# AnyTelemetry.net
KiCad netlist of a schematic drawn in EAGLE
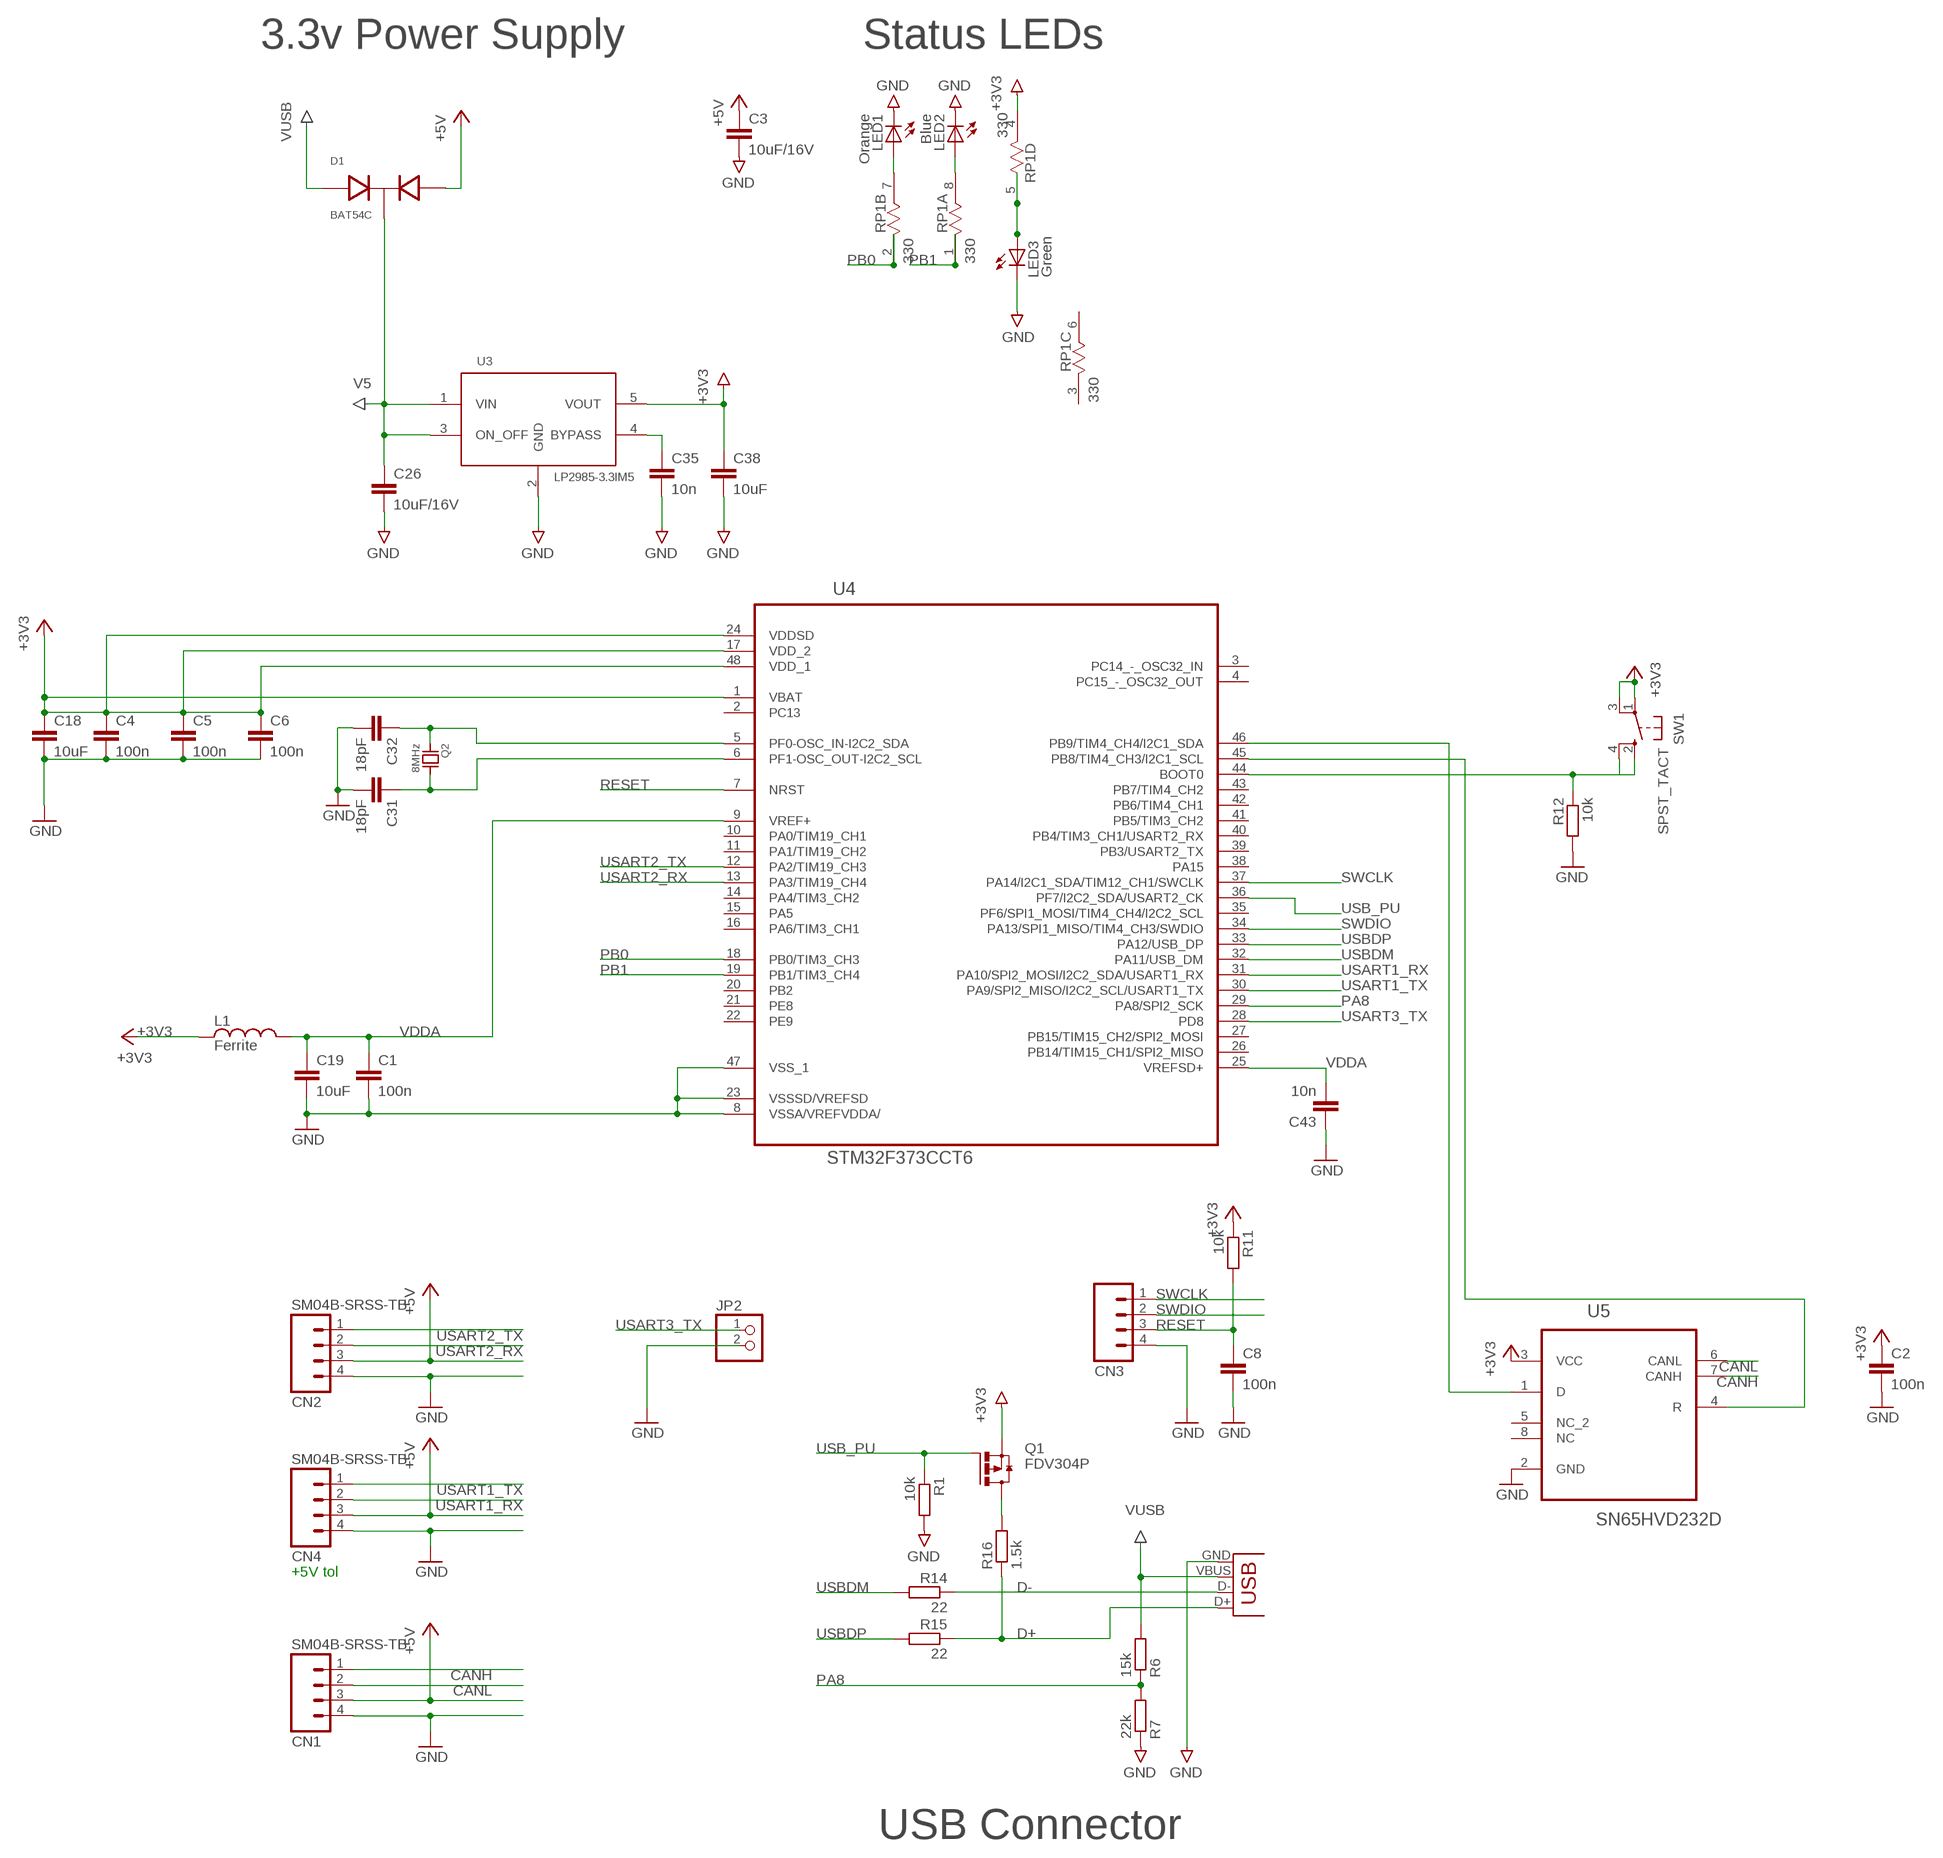
[diagram p0: schematic, sheet 1]

(export (version "E")
  (design (tool "Eeschema 10.0.6"))
  (components
    (comp (ref "C1")
      (value "100n")
      (footprint "eagle-import:0603")
      (libsource (lib "eagle-import") (part "CAPACITOR0603"))
    )
    (comp (ref "C2")
      (value "100n")
      (footprint "eagle-import:0603")
      (libsource (lib "eagle-import") (part "CAPACITOR0603"))
    )
    (comp (ref "C3")
      (value "10uF/16V")
      (footprint "eagle-import:C0805")
      (libsource (lib "eagle-import") (part "C-EUC0805"))
    )
    (comp (ref "C4")
      (value "100n")
      (footprint "eagle-import:0603")
      (libsource (lib "eagle-import") (part "CAPACITOR0603"))
    )
    (comp (ref "C5")
      (value "100n")
      (footprint "eagle-import:0603")
      (libsource (lib "eagle-import") (part "CAPACITOR0603"))
    )
    (comp (ref "C6")
      (value "100n")
      (footprint "eagle-import:0603")
      (libsource (lib "eagle-import") (part "CAPACITOR0603"))
    )
    (comp (ref "C8")
      (value "100n")
      (footprint "eagle-import:0603")
      (libsource (lib "eagle-import") (part "CAPACITOR0603"))
    )
    (comp (ref "C18")
      (value "10uF")
      (footprint "eagle-import:C0805")
      (libsource (lib "eagle-import") (part "C-EUC0805"))
    )
    (comp (ref "C19")
      (value "10uF")
      (footprint "eagle-import:C0805")
      (libsource (lib "eagle-import") (part "C-EUC0805"))
    )
    (comp (ref "C26")
      (value "10uF/16V")
      (footprint "eagle-import:C0805")
      (libsource (lib "eagle-import") (part "C-EUC0805"))
    )
    (comp (ref "C31")
      (value "18pF")
      (footprint "eagle-import:0603")
      (libsource (lib "eagle-import") (part "CAPACITOR0603"))
    )
    (comp (ref "C32")
      (value "18pF")
      (footprint "eagle-import:0603")
      (libsource (lib "eagle-import") (part "CAPACITOR0603"))
    )
    (comp (ref "C35")
      (value "10n")
      (footprint "eagle-import:C0603")
      (libsource (lib "eagle-import") (part "C-EUC0603"))
    )
    (comp (ref "C38")
      (value "10uF")
      (footprint "eagle-import:C0805")
      (libsource (lib "eagle-import") (part "C-EUC0805"))
    )
    (comp (ref "C43")
      (value "10n")
      (footprint "eagle-import:0603-CAP")
      (libsource (lib "eagle-import") (part "CAP0603-CAP"))
    )
    (comp (ref "CN1")
      (value "SM04B-SRSS-TB")
      (footprint "eagle-import:SM04B-SRSS-TB")
      (libsource (lib "eagle-import") (part "SM04B-SRSS-TB"))
    )
    (comp (ref "CN2")
      (value "SM04B-SRSS-TB")
      (footprint "eagle-import:SM04B-SRSS-TB")
      (libsource (lib "eagle-import") (part "SM04B-SRSS-TB"))
    )
    (comp (ref "CN3")
      (value "SM04B-SRSS-TB")
      (footprint "eagle-import:SM04B-SRSS-TB")
      (libsource (lib "eagle-import") (part "SM04B-SRSS-TB"))
    )
    (comp (ref "CN4")
      (value "SM04B-SRSS-TB")
      (footprint "eagle-import:SM04B-SRSS-TB")
      (libsource (lib "eagle-import") (part "SM04B-SRSS-TB"))
    )
    (comp (ref "D1")
      (value "BAT54C")
      (footprint "eagle-import:SOT23")
      (libsource (lib "eagle-import") (part "BAT54C"))
    )
    (comp (ref "JP2")
      (value "PINHD-1X02_2.54-S")
      (footprint "eagle-import:1X02-S")
      (libsource (lib "eagle-import") (part "PINHD-1X02_2.54-S"))
    )
    (comp (ref "L1")
      (value "Ferrite")
      (footprint "eagle-import:0603")
      (libsource (lib "eagle-import") (part "INDUCTOR0603"))
    )
    (comp (ref "LED1")
      (value "Orange")
      (footprint "eagle-import:CHIPLED_0603")
      (libsource (lib "eagle-import") (part "LEDCHIPLED_0603"))
    )
    (comp (ref "LED2")
      (value "Blue")
      (footprint "eagle-import:CHIPLED_0603")
      (libsource (lib "eagle-import") (part "LEDCHIPLED_0603"))
    )
    (comp (ref "LED3")
      (value "Green")
      (footprint "eagle-import:CHIPLED_0603")
      (libsource (lib "eagle-import") (part "LEDCHIPLED_0603"))
    )
    (comp (ref "Q1")
      (value "FDV304P")
      (footprint "eagle-import:SUPER-SOT3")
      (libsource (lib "eagle-import") (part "FDN360P"))
    )
    (comp (ref "Q2")
      (value "8MHz")
      (footprint "eagle-import:CRYSTAL-5X3")
      (libsource (lib "eagle-import") (part "CRYSTAL-5X3"))
    )
    (comp (ref "R1")
      (value "10k")
      (footprint "eagle-import:R0603")
      (libsource (lib "eagle-import") (part "R-EU_R0603"))
    )
    (comp (ref "R6")
      (value "15k")
      (footprint "eagle-import:R0603")
      (libsource (lib "eagle-import") (part "R-EU_R0603"))
    )
    (comp (ref "R7")
      (value "22k")
      (footprint "eagle-import:R0603")
      (libsource (lib "eagle-import") (part "R-EU_R0603"))
    )
    (comp (ref "R11")
      (value "10k")
      (footprint "eagle-import:R0603")
      (libsource (lib "eagle-import") (part "R-EU_R0603"))
    )
    (comp (ref "R12")
      (value "10k")
      (footprint "eagle-import:R0603")
      (libsource (lib "eagle-import") (part "R-EU_R0603"))
    )
    (comp (ref "R14")
      (value "22")
      (footprint "eagle-import:R0603")
      (libsource (lib "eagle-import") (part "R-EU_R0603"))
    )
    (comp (ref "R15")
      (value "22")
      (footprint "eagle-import:R0603")
      (libsource (lib "eagle-import") (part "R-EU_R0603"))
    )
    (comp (ref "R16")
      (value "1.5k")
      (footprint "eagle-import:R0603")
      (libsource (lib "eagle-import") (part "R-EU_R0603"))
    )
    (comp (ref "RP1")
      (value "330")
      (footprint "eagle-import:RES4NT")
      (libsource (lib "eagle-import") (part "RES4NT"))
    )
    (comp (ref "SW1")
      (value "SPST_TACT")
      (footprint "eagle-import:EVQ-PU")
      (libsource (lib "eagle-import") (part "SPST_TACT"))
    )
    (comp (ref "U3")
      (value "LP2985-3.3IM5")
      (footprint "eagle-import:SOT23-5")
      (libsource (lib "eagle-import") (part "LP2985-IM53.3"))
    )
    (comp (ref "U4")
      (value "STM32F373CCT6")
      (footprint "eagle-import:QFP50P900X900X160-48N")
      (libsource (lib "eagle-import") (part "STM32F373CCT6"))
    )
    (comp (ref "U5")
      (value "SN65HVD232D")
      (footprint "eagle-import:SOIC127P600X175-8N")
      (libsource (lib "eagle-import") (part "SN65HVD232D"))
    )
    (comp (ref "X2")
      (value "USBSMD")
      (footprint "eagle-import:USB-MINIB")
      (libsource (lib "eagle-import") (part "USBSMD"))
    )
  )
  (nets
    (net (code "1") (name "+3V3") (class "Default")
      (node (ref "C18") (pin "1") (pinfunction "1_1") (pintype "passive"))
      (node (ref "C2") (pin "1") (pinfunction "1_1") (pintype "passive"))
      (node (ref "C38") (pin "1") (pinfunction "1_1") (pintype "passive"))
      (node (ref "C4") (pin "1") (pinfunction "1_1") (pintype "passive"))
      (node (ref "C5") (pin "1") (pinfunction "1_1") (pintype "passive"))
      (node (ref "C6") (pin "1") (pinfunction "1_1") (pintype "passive"))
      (node (ref "L1") (pin "1") (pinfunction "1_1") (pintype "passive"))
      (node (ref "Q1") (pin "2") (pinfunction "S_2") (pintype "passive"))
      (node (ref "R11") (pin "1") (pinfunction "1_1") (pintype "passive"))
      (node (ref "RP1") (pin "4") (pinfunction "1_4") (pintype "passive"))
      (node (ref "SW1") (pin "1") (pinfunction "P_1") (pintype "passive"))
      (node (ref "SW1") (pin "3") (pinfunction "P1_3") (pintype "passive"))
      (node (ref "U3") (pin "5") (pinfunction "VOUT_5") (pintype "passive"))
      (node (ref "U4") (pin "1") (pinfunction "VBAT_1") (pintype "passive"))
      (node (ref "U4") (pin "17") (pinfunction "VDD_2_17") (pintype "power_in"))
      (node (ref "U4") (pin "24") (pinfunction "VDDSD_24") (pintype "power_in"))
      (node (ref "U4") (pin "48") (pinfunction "VDD_1_48") (pintype "power_in"))
      (node (ref "U5") (pin "3") (pinfunction "VCC_3") (pintype "power_in"))
    )
    (net (code "2") (name "+5V") (class "Default")
      (node (ref "C3") (pin "1") (pinfunction "1_1") (pintype "passive"))
      (node (ref "CN1") (pin "3") (pinfunction "3_3") (pintype "passive"))
      (node (ref "CN2") (pin "3") (pinfunction "3_3") (pintype "passive"))
      (node (ref "CN4") (pin "3") (pinfunction "3_3") (pintype "passive"))
      (node (ref "D1") (pin "2") (pinfunction "P$2_2") (pintype "input"))
    )
    (net (code "3") (name "/CANH") (class "Default")
      (node (ref "CN1") (pin "1") (pinfunction "1_1") (pintype "passive"))
      (node (ref "U5") (pin "7") (pinfunction "CANH_7") (pintype "output"))
    )
    (net (code "4") (name "/CANL") (class "Default")
      (node (ref "CN1") (pin "2") (pinfunction "2_2") (pintype "passive"))
      (node (ref "U5") (pin "6") (pinfunction "CANL_6") (pintype "output"))
    )
    (net (code "5") (name "/D+") (class "Default")
      (node (ref "R15") (pin "1") (pinfunction "1_1") (pintype "passive"))
      (node (ref "R16") (pin "1") (pinfunction "1_1") (pintype "passive"))
      (node (ref "X2") (pin "D+") (pinfunction "D+_D+") (pintype "bidirectional"))
    )
    (net (code "6") (name "/D-") (class "Default")
      (node (ref "R14") (pin "1") (pinfunction "1_1") (pintype "passive"))
      (node (ref "X2") (pin "D-") (pinfunction "D-_D-") (pintype "bidirectional"))
    )
    (net (code "7") (name "/PA8") (class "Default")
      (node (ref "R6") (pin "1") (pinfunction "1_1") (pintype "passive"))
      (node (ref "R7") (pin "2") (pinfunction "2_2") (pintype "passive"))
      (node (ref "U4") (pin "29") (pinfunction "PA8/SPI2_SCK_29") (pintype "bidirectional"))
    )
    (net (code "8") (name "/PB0") (class "Default")
      (node (ref "RP1") (pin "2") (pinfunction "1_2") (pintype "passive"))
      (node (ref "U4") (pin "18") (pinfunction "PB0/TIM3_CH3_18") (pintype "bidirectional"))
    )
    (net (code "9") (name "/PB1") (class "Default")
      (node (ref "RP1") (pin "1") (pinfunction "1_1") (pintype "passive"))
      (node (ref "U4") (pin "19") (pinfunction "PB1/TIM3_CH4_19") (pintype "bidirectional"))
    )
    (net (code "10") (name "/RESET") (class "Default")
      (node (ref "C8") (pin "1") (pinfunction "1_1") (pintype "passive"))
      (node (ref "CN3") (pin "3") (pinfunction "3_3") (pintype "passive"))
      (node (ref "R11") (pin "2") (pinfunction "2_2") (pintype "passive"))
      (node (ref "U4") (pin "7") (pinfunction "NRST_7") (pintype "passive"))
    )
    (net (code "11") (name "/SWCLK") (class "Default")
      (node (ref "CN3") (pin "1") (pinfunction "1_1") (pintype "passive"))
      (node (ref "U4") (pin "37") (pinfunction "PA14/I2C1_SDA/TIM12_CH1/SWCLK_37") (pintype "bidirectional"))
    )
    (net (code "12") (name "/SWDIO") (class "Default")
      (node (ref "CN3") (pin "2") (pinfunction "2_2") (pintype "passive"))
      (node (ref "U4") (pin "34") (pinfunction "PA13/SPI1_MISO/TIM4_CH3/SWDIO_34") (pintype "bidirectional"))
    )
    (net (code "13") (name "/USART1_RX") (class "Default")
      (node (ref "CN4") (pin "2") (pinfunction "2_2") (pintype "passive"))
      (node (ref "U4") (pin "31") (pinfunction "PA10/SPI2_MOSI/I2C2_SDA/USART1_RX_31") (pintype "bidirectional"))
    )
    (net (code "14") (name "/USART1_TX") (class "Default")
      (node (ref "CN4") (pin "1") (pinfunction "1_1") (pintype "passive"))
      (node (ref "U4") (pin "30") (pinfunction "PA9/SPI2_MISO/I2C2_SCL/USART1_TX_30") (pintype "bidirectional"))
    )
    (net (code "15") (name "/USART2_RX") (class "Default")
      (node (ref "CN2") (pin "2") (pinfunction "2_2") (pintype "passive"))
      (node (ref "U4") (pin "13") (pinfunction "PA3/TIM19_CH4_13") (pintype "bidirectional"))
    )
    (net (code "16") (name "/USART2_TX") (class "Default")
      (node (ref "CN2") (pin "1") (pinfunction "1_1") (pintype "passive"))
      (node (ref "U4") (pin "12") (pinfunction "PA2/TIM19_CH3_12") (pintype "bidirectional"))
    )
    (net (code "17") (name "/USART3_TX") (class "Default")
      (node (ref "JP2") (pin "1") (pinfunction "1_1") (pintype "passive"))
      (node (ref "U4") (pin "28") (pinfunction "PD8_28") (pintype "bidirectional"))
    )
    (net (code "18") (name "/USBDM") (class "Default")
      (node (ref "R14") (pin "2") (pinfunction "2_2") (pintype "passive"))
      (node (ref "U4") (pin "32") (pinfunction "PA11/USB_DM_32") (pintype "bidirectional"))
    )
    (net (code "19") (name "/USBDP") (class "Default")
      (node (ref "R15") (pin "2") (pinfunction "2_2") (pintype "passive"))
      (node (ref "U4") (pin "33") (pinfunction "PA12/USB_DP_33") (pintype "bidirectional"))
    )
    (net (code "20") (name "/USB_PU") (class "Default")
      (node (ref "Q1") (pin "1") (pinfunction "G_1") (pintype "passive"))
      (node (ref "R1") (pin "1") (pinfunction "1_1") (pintype "passive"))
      (node (ref "U4") (pin "36") (pinfunction "PF7/I2C2_SDA/USART2_CK_36") (pintype "bidirectional"))
    )
    (net (code "21") (name "/V5") (class "Default")
      (node (ref "C26") (pin "1") (pinfunction "1_1") (pintype "passive"))
      (node (ref "D1") (pin "3") (pinfunction "P$3_3") (pintype "output"))
      (node (ref "U3") (pin "1") (pinfunction "VIN_1") (pintype "power_in"))
      (node (ref "U3") (pin "3") (pinfunction "ON_OFF_3") (pintype "input"))
    )
    (net (code "22") (name "/VDDA") (class "Default")
      (node (ref "C1") (pin "1") (pinfunction "1_1") (pintype "passive"))
      (node (ref "C19") (pin "1") (pinfunction "1_1") (pintype "passive"))
      (node (ref "C43") (pin "2") (pinfunction "2_2") (pintype "passive"))
      (node (ref "L1") (pin "2") (pinfunction "2_2") (pintype "passive"))
      (node (ref "U4") (pin "25") (pinfunction "VREFSD+_25") (pintype "passive"))
      (node (ref "U4") (pin "9") (pinfunction "VREF+_9") (pintype "passive"))
    )
    (net (code "23") (name "/VUSB") (class "Default")
      (node (ref "D1") (pin "1") (pinfunction "P$1_1") (pintype "input"))
      (node (ref "R6") (pin "2") (pinfunction "2_2") (pintype "passive"))
      (node (ref "X2") (pin "VBUS") (pinfunction "VBUS_VBUS") (pintype "bidirectional"))
    )
    (net (code "24") (name "GND") (class "Default")
      (node (ref "C1") (pin "2") (pinfunction "2_2") (pintype "passive"))
      (node (ref "C18") (pin "2") (pinfunction "2_2") (pintype "passive"))
      (node (ref "C19") (pin "2") (pinfunction "2_2") (pintype "passive"))
      (node (ref "C2") (pin "2") (pinfunction "2_2") (pintype "passive"))
      (node (ref "C26") (pin "2") (pinfunction "2_2") (pintype "passive"))
      (node (ref "C3") (pin "2") (pinfunction "2_2") (pintype "passive"))
      (node (ref "C31") (pin "2") (pinfunction "2_2") (pintype "passive"))
      (node (ref "C32") (pin "2") (pinfunction "2_2") (pintype "passive"))
      (node (ref "C35") (pin "2") (pinfunction "2_2") (pintype "passive"))
      (node (ref "C38") (pin "2") (pinfunction "2_2") (pintype "passive"))
      (node (ref "C4") (pin "2") (pinfunction "2_2") (pintype "passive"))
      (node (ref "C43") (pin "1") (pinfunction "1_1") (pintype "passive"))
      (node (ref "C5") (pin "2") (pinfunction "2_2") (pintype "passive"))
      (node (ref "C6") (pin "2") (pinfunction "2_2") (pintype "passive"))
      (node (ref "C8") (pin "2") (pinfunction "2_2") (pintype "passive"))
      (node (ref "CN1") (pin "4") (pinfunction "4_4") (pintype "passive"))
      (node (ref "CN2") (pin "4") (pinfunction "4_4") (pintype "passive"))
      (node (ref "CN3") (pin "4") (pinfunction "4_4") (pintype "passive"))
      (node (ref "CN4") (pin "4") (pinfunction "4_4") (pintype "passive"))
      (node (ref "JP2") (pin "2") (pinfunction "2_2") (pintype "passive"))
      (node (ref "LED1") (pin "C") (pinfunction "C_C") (pintype "passive"))
      (node (ref "LED2") (pin "C") (pinfunction "C_C") (pintype "passive"))
      (node (ref "LED3") (pin "C") (pinfunction "C_C") (pintype "passive"))
      (node (ref "R1") (pin "2") (pinfunction "2_2") (pintype "passive"))
      (node (ref "R12") (pin "2") (pinfunction "2_2") (pintype "passive"))
      (node (ref "R7") (pin "1") (pinfunction "1_1") (pintype "passive"))
      (node (ref "U3") (pin "2") (pinfunction "GND_2") (pintype "power_in"))
      (node (ref "U4") (pin "23") (pinfunction "VSSSD/VREFSD_23") (pintype "power_in"))
      (node (ref "U4") (pin "47") (pinfunction "VSS_1_47") (pintype "power_in"))
      (node (ref "U4") (pin "8") (pinfunction "VSSA/VREFVDDA/_8") (pintype "power_in"))
      (node (ref "U5") (pin "2") (pinfunction "GND_2") (pintype "passive"))
      (node (ref "X2") (pin "GND") (pinfunction "GND_GND") (pintype "bidirectional"))
    )
    (net (code "25") (name "Net-(Q1-D)") (class "Default")
      (node (ref "Q1") (pin "3") (pinfunction "D_3") (pintype "passive"))
      (node (ref "R16") (pin "2") (pinfunction "2_2") (pintype "passive"))
    )
    (net (code "26") (name "Net-(Q2-2)") (class "Default")
      (node (ref "C31") (pin "1") (pinfunction "1_1") (pintype "passive"))
      (node (ref "Q2") (pin "3") (pinfunction "2_3") (pintype "passive"))
      (node (ref "U4") (pin "6") (pinfunction "PF1-OSC_OUT-I2C2_SCL_6") (pintype "bidirectional"))
    )
    (net (code "27") (name "Net-(RP1A-2)") (class "Default")
      (node (ref "LED2") (pin "A") (pinfunction "A_A") (pintype "passive"))
      (node (ref "RP1") (pin "8") (pinfunction "2_8") (pintype "passive"))
    )
    (net (code "28") (name "Net-(RP1B-2)") (class "Default")
      (node (ref "LED1") (pin "A") (pinfunction "A_A") (pintype "passive"))
      (node (ref "RP1") (pin "7") (pinfunction "2_7") (pintype "passive"))
    )
    (net (code "29") (name "Net-(RP1D-2)") (class "Default")
      (node (ref "LED3") (pin "A") (pinfunction "A_A") (pintype "passive"))
      (node (ref "RP1") (pin "5") (pinfunction "2_5") (pintype "passive"))
    )
    (net (code "30") (name "Net-(SW1-S)") (class "Default")
      (node (ref "R12") (pin "1") (pinfunction "1_1") (pintype "passive"))
      (node (ref "SW1") (pin "2") (pinfunction "S_2") (pintype "passive"))
      (node (ref "SW1") (pin "4") (pinfunction "S1_4") (pintype "passive"))
      (node (ref "U4") (pin "44") (pinfunction "BOOT0_44") (pintype "passive"))
    )
    (net (code "31") (name "Net-(U3-BYPASS)") (class "Default")
      (node (ref "C35") (pin "1") (pinfunction "1_1") (pintype "passive"))
      (node (ref "U3") (pin "4") (pinfunction "BYPASS_4") (pintype "input"))
    )
    (net (code "32") (name "Net-(U4-PB8{slash}TIM4_CH3{slash}I2C1_SCL)") (class "Default")
      (node (ref "U4") (pin "45") (pinfunction "PB8/TIM4_CH3/I2C1_SCL_45") (pintype "bidirectional"))
      (node (ref "U5") (pin "4") (pinfunction "R_4") (pintype "output"))
    )
    (net (code "33") (name "Net-(U4-PB9{slash}TIM4_CH4{slash}I2C1_SDA)") (class "Default")
      (node (ref "U4") (pin "46") (pinfunction "PB9/TIM4_CH4/I2C1_SDA_46") (pintype "bidirectional"))
      (node (ref "U5") (pin "1") (pinfunction "D_1") (pintype "input"))
    )
    (net (code "34") (name "Net-(U4-PF0-OSC_IN-I2C2_SDA)") (class "Default")
      (node (ref "C32") (pin "1") (pinfunction "1_1") (pintype "passive"))
      (node (ref "Q2") (pin "1") (pinfunction "1_1") (pintype "passive"))
      (node (ref "U4") (pin "5") (pinfunction "PF0-OSC_IN-I2C2_SDA_5") (pintype "bidirectional"))
    )
    (net (code "35") (name "unconnected-(RP1C-1-Pad3)") (class "Default")
      (node (ref "RP1") (pin "3") (pinfunction "1_3") (pintype "passive"))
    )
    (net (code "36") (name "unconnected-(RP1C-2-Pad6)") (class "Default")
      (node (ref "RP1") (pin "6") (pinfunction "2_6") (pintype "passive"))
    )
    (net (code "37") (name "unconnected-(U4-PA0{slash}TIM19_CH1-Pad10)") (class "Default")
      (node (ref "U4") (pin "10") (pinfunction "PA0/TIM19_CH1_10") (pintype "bidirectional"))
    )
    (net (code "38") (name "unconnected-(U4-PA1{slash}TIM19_CH2-Pad11)") (class "Default")
      (node (ref "U4") (pin "11") (pinfunction "PA1/TIM19_CH2_11") (pintype "bidirectional"))
    )
    (net (code "39") (name "unconnected-(U4-PA4{slash}TIM3_CH2-Pad14)") (class "Default")
      (node (ref "U4") (pin "14") (pinfunction "PA4/TIM3_CH2_14") (pintype "bidirectional"))
    )
    (net (code "40") (name "unconnected-(U4-PA5-Pad15)") (class "Default")
      (node (ref "U4") (pin "15") (pinfunction "PA5_15") (pintype "bidirectional"))
    )
    (net (code "41") (name "unconnected-(U4-PA6{slash}TIM3_CH1-Pad16)") (class "Default")
      (node (ref "U4") (pin "16") (pinfunction "PA6/TIM3_CH1_16") (pintype "bidirectional"))
    )
    (net (code "42") (name "unconnected-(U4-PA15-Pad38)") (class "Default")
      (node (ref "U4") (pin "38") (pinfunction "PA15_38") (pintype "bidirectional"))
    )
    (net (code "43") (name "unconnected-(U4-PB2-Pad20)") (class "Default")
      (node (ref "U4") (pin "20") (pinfunction "PB2_20") (pintype "bidirectional"))
    )
    (net (code "44") (name "unconnected-(U4-PB3{slash}USART2_TX-Pad39)") (class "Default")
      (node (ref "U4") (pin "39") (pinfunction "PB3/USART2_TX_39") (pintype "bidirectional"))
    )
    (net (code "45") (name "unconnected-(U4-PB4{slash}TIM3_CH1{slash}USART2_RX-Pad40)") (class "Default")
      (node (ref "U4") (pin "40") (pinfunction "PB4/TIM3_CH1/USART2_RX_40") (pintype "bidirectional"))
    )
    (net (code "46") (name "unconnected-(U4-PB5{slash}TIM3_CH2-Pad41)") (class "Default")
      (node (ref "U4") (pin "41") (pinfunction "PB5/TIM3_CH2_41") (pintype "bidirectional"))
    )
    (net (code "47") (name "unconnected-(U4-PB6{slash}TIM4_CH1-Pad42)") (class "Default")
      (node (ref "U4") (pin "42") (pinfunction "PB6/TIM4_CH1_42") (pintype "bidirectional"))
    )
    (net (code "48") (name "unconnected-(U4-PB7{slash}TIM4_CH2-Pad43)") (class "Default")
      (node (ref "U4") (pin "43") (pinfunction "PB7/TIM4_CH2_43") (pintype "bidirectional"))
    )
    (net (code "49") (name "unconnected-(U4-PB14{slash}TIM15_CH1{slash}SPI2_MISO-Pad26)") (class "Default")
      (node (ref "U4") (pin "26") (pinfunction "PB14/TIM15_CH1/SPI2_MISO_26") (pintype "bidirectional"))
    )
    (net (code "50") (name "unconnected-(U4-PB15{slash}TIM15_CH2{slash}SPI2_MOSI-Pad27)") (class "Default")
      (node (ref "U4") (pin "27") (pinfunction "PB15/TIM15_CH2/SPI2_MOSI_27") (pintype "bidirectional"))
    )
    (net (code "51") (name "unconnected-(U4-PC13-Pad2)") (class "Default")
      (node (ref "U4") (pin "2") (pinfunction "PC13_2") (pintype "bidirectional"))
    )
    (net (code "52") (name "unconnected-(U4-PC14_-_OSC32_IN-Pad3)") (class "Default")
      (node (ref "U4") (pin "3") (pinfunction "PC14_-_OSC32_IN_3") (pintype "bidirectional"))
    )
    (net (code "53") (name "unconnected-(U4-PC15_-_OSC32_OUT-Pad4)") (class "Default")
      (node (ref "U4") (pin "4") (pinfunction "PC15_-_OSC32_OUT_4") (pintype "bidirectional"))
    )
    (net (code "54") (name "unconnected-(U4-PE8-Pad21)") (class "Default")
      (node (ref "U4") (pin "21") (pinfunction "PE8_21") (pintype "bidirectional"))
    )
    (net (code "55") (name "unconnected-(U4-PE9-Pad22)") (class "Default")
      (node (ref "U4") (pin "22") (pinfunction "PE9_22") (pintype "bidirectional"))
    )
    (net (code "56") (name "unconnected-(U4-PF6{slash}SPI1_MOSI{slash}TIM4_CH4{slash}I2C2_SCL-Pad35)") (class "Default")
      (node (ref "U4") (pin "35") (pinfunction "PF6/SPI1_MOSI/TIM4_CH4/I2C2_SCL_35") (pintype "bidirectional"))
    )
    (net (code "57") (name "unconnected-(U5-NC-Pad8)") (class "Default")
      (node (ref "U5") (pin "8") (pinfunction "NC_8") (pintype "no_connect"))
    )
    (net (code "58") (name "unconnected-(U5-NC_2-Pad5)") (class "Default")
      (node (ref "U5") (pin "5") (pinfunction "NC_2_5") (pintype "no_connect"))
    )
  )
)
